# Real_Time_Clock.net
KiCad netlist of a schematic drawn in Altium Designer
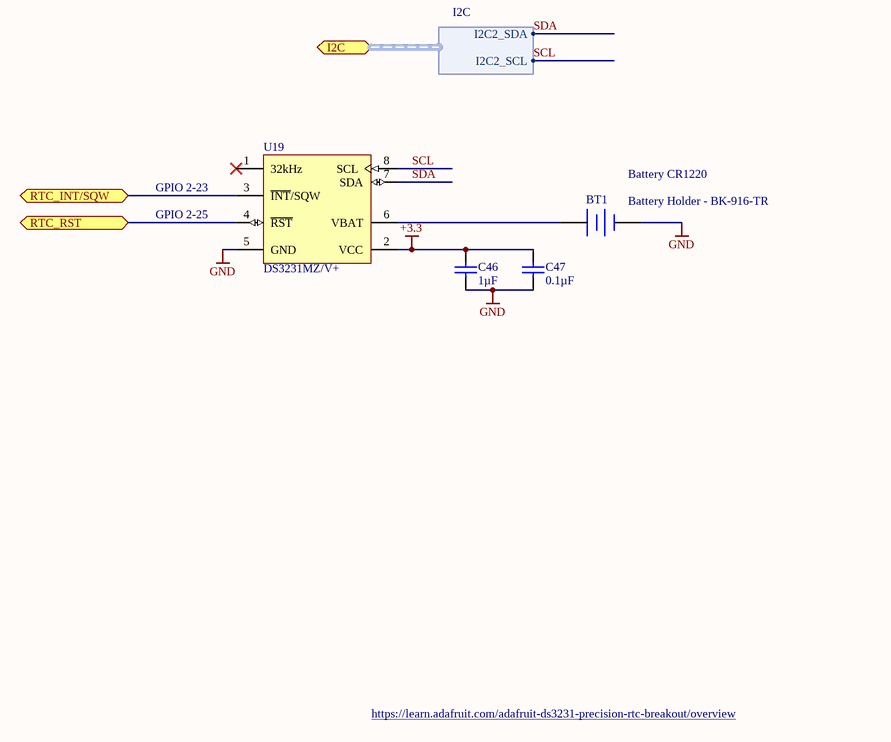
[diagram p0: Real Time Clock.SchDoc]

(export (version "E")
  (design (tool "Eeschema 10.0.6"))
  (components
    (comp (ref "BT1")
      (value "Battery Holder - BK-916-TR")
      (footprint "BK-916-TR")
      (description "CR1220, 1225 BATTERY RETAINER W/")
      (libsource (lib "Miscellaneous Devices") (part "Battery"))
    )
    (comp (ref "C46")
      (value "CAP 1uF 25V 0805(2012)")
      (footprint "CAPC0805(2012)100_M")
      (description "CAP 1uF 25V ±10% 0805 (2012 Metric) Thickness 1mm SMD")
      (fields
        (field (name "MANUFACTURER") "Murata Electronics North America")
        (field (name "MANUFACTURER PART NUMBER") "GRM21BR71E105KA99L")
        (field (name "CAPACITANCE") "1µF")
      )
      (libsource (lib "Altium Content Vault") (part "CMP-1036-04754-1"))
    )
    (comp (ref "C47")
      (value "CAP 100nF 25V 0805(2012)")
      (footprint "CAPC0805(2012)100_N")
      (description "CAP 100nF 25V -20% to +80% 0805 (2012 Metric) Thickness 1mm SMD")
      (fields
        (field (name "MANUFACTURER") "Murata Electronics North America")
        (field (name "MANUFACTURER PART NUMBER") "GRM21BR71E104KA01L")
        (field (name "CAPACITANCE") "0.1µF")
      )
      (libsource (lib "Altium Content Vault") (part "CMP-1036-04416-1"))
    )
    (comp (ref "U19")
      (value "DS3231MZ/V+")
      (footprint "S8MK+1_N")
      (libsource (lib "Altium Content Vault") (part "CMP-0254-00374-1"))
    )
  )
  (nets
    (net (code "2") (name "+3.3") (class "Default")
      (node (ref "C46") (pin "1") (pinfunction "1_1") (pintype "passive"))
      (node (ref "C47") (pin "1") (pinfunction "1_1") (pintype "passive"))
      (node (ref "U19") (pin "2") (pinfunction "VCC_2") (pintype "power_in"))
    )
    (net (code "3") (name "/RTC_INT{slash}SQW") (class "Default")
      (node (ref "U19") (pin "3") (pinfunction "~{INT}/SQW_3") (pintype "open_collector"))
    )
    (net (code "4") (name "/RTC_RST") (class "Default")
      (node (ref "U19") (pin "4") (pinfunction "~{RST}_4") (pintype "bidirectional"))
    )
    (net (code "5") (name "/SCL") (class "Default")
      (node (ref "U19") (pin "8") (pinfunction "SCL_8") (pintype "input"))
    )
    (net (code "6") (name "/SDA") (class "Default")
      (node (ref "U19") (pin "7") (pinfunction "SDA_7") (pintype "bidirectional"))
    )
    (net (code "8") (name "GND") (class "Default")
      (node (ref "BT1") (pin "2") (pinfunction "-_2") (pintype "passive"))
      (node (ref "C46") (pin "2") (pinfunction "2_2") (pintype "passive"))
      (node (ref "C47") (pin "2") (pinfunction "2_2") (pintype "passive"))
      (node (ref "U19") (pin "5") (pinfunction "GND_5") (pintype "power_in"))
    )
    (net (code "9") (name "Net-(BT1-+)") (class "Default")
      (node (ref "BT1") (pin "1") (pinfunction "+_1") (pintype "passive"))
      (node (ref "U19") (pin "6") (pinfunction "VBAT_6") (pintype "power_in"))
    )
    (net (code "10") (name "unconnected-(U19-32kHz-Pad1)") (class "Default")
      (node (ref "U19") (pin "1") (pinfunction "32kHz_1") (pintype "open_collector+no_connect"))
    )
  )
)
